# KursSCH4.net
KiCad netlist of a schematic drawn in Altium Designer
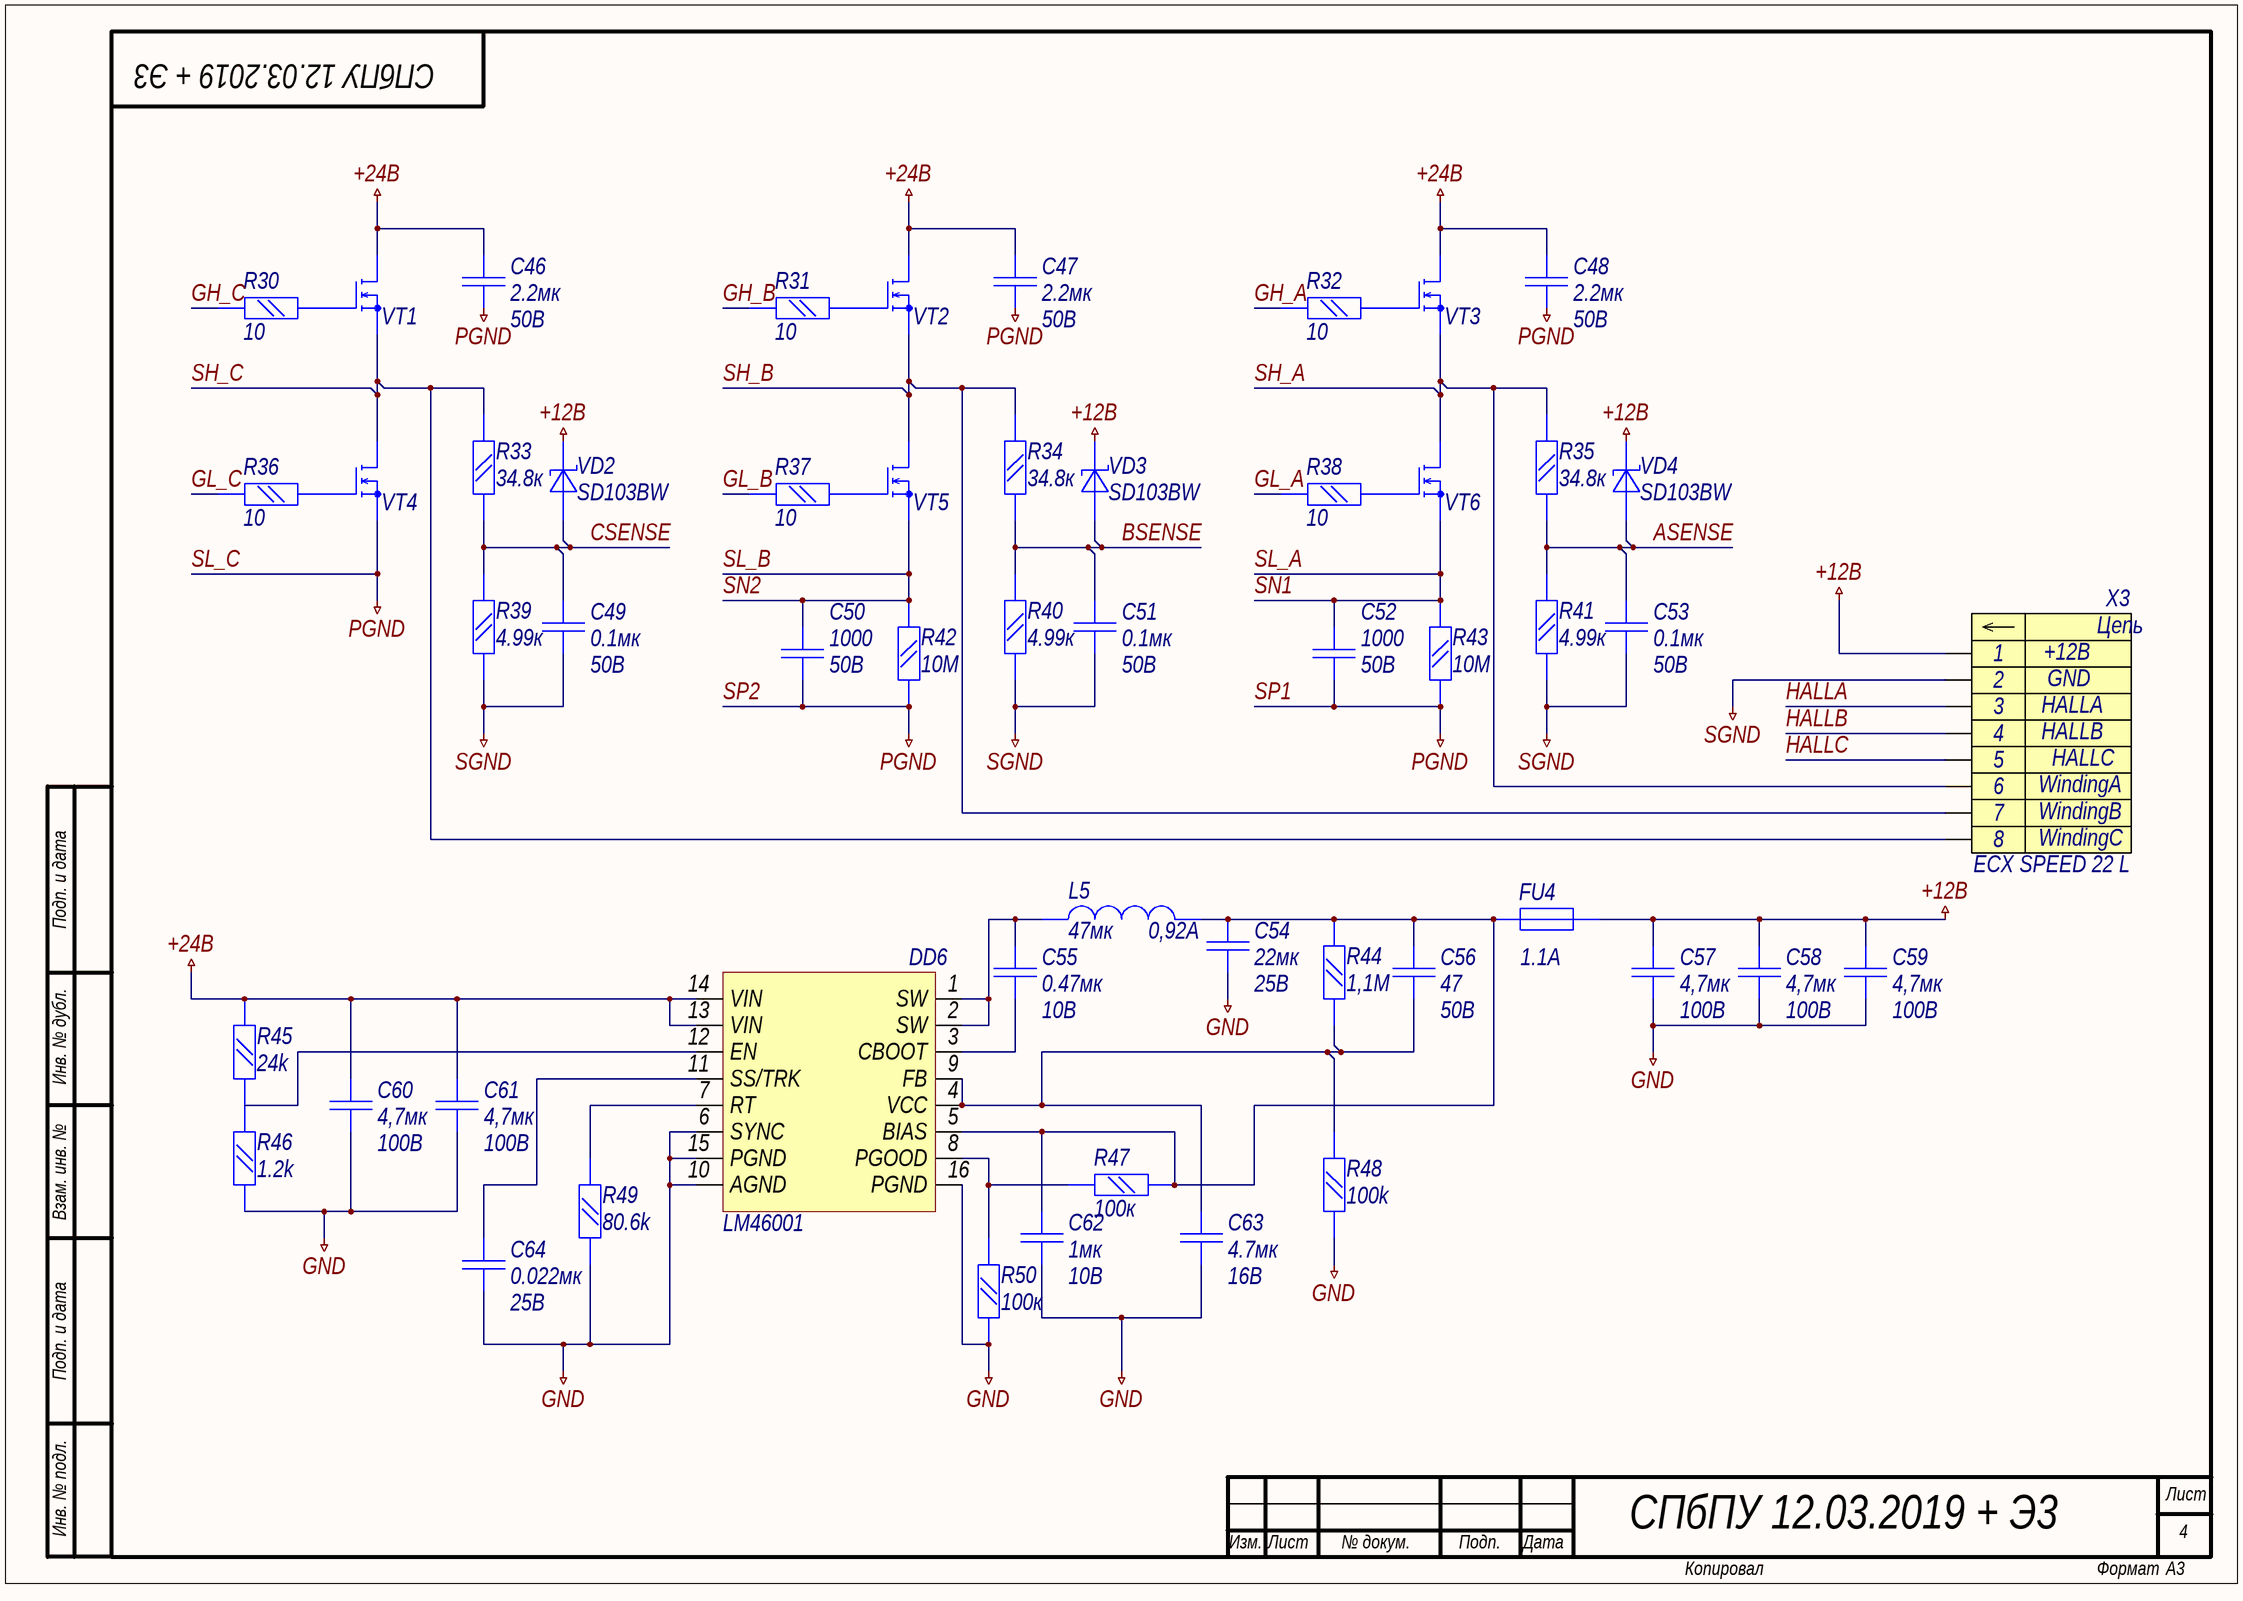
[diagram p0: KursSCH4.schdoc]

(export (version "E")
  (design (tool "Eeschema 10.0.6"))
  (components
    (comp (ref "C46")
      (value "2.2мк")
      (footprint "C0603")
      (fields
        (field (name "VOLTAGE") "50В")
        (field (name "PART NUMBER") "GRM188R61C225KE15D")
        (field (name "TOLERANCE") "±10%")
        (field (name "MANUFACTURER") "Murata")
      )
      (libsource (lib "Lib_IMP_GOST") (part "Capacitor"))
    )
    (comp (ref "C47")
      (value "2.2мк")
      (footprint "C0603")
      (fields
        (field (name "VOLTAGE") "50В")
        (field (name "PART NUMBER") "GRM188R61C225KE15D")
        (field (name "TOLERANCE") "±10%")
        (field (name "MANUFACTURER") "Murata")
      )
      (libsource (lib "Lib_IMP_GOST") (part "Capacitor"))
    )
    (comp (ref "C48")
      (value "2.2мк")
      (footprint "C0603")
      (fields
        (field (name "VOLTAGE") "50В")
        (field (name "PART NUMBER") "GRM188R61C225KE15D")
        (field (name "TOLERANCE") "±10%")
        (field (name "MANUFACTURER") "Murata")
      )
      (libsource (lib "Lib_IMP_GOST") (part "Capacitor"))
    )
    (comp (ref "C49")
      (value "0.1мк")
      (footprint "C0805")
      (fields
        (field (name "VOLTAGE") "50В")
        (field (name "PART NUMBER") "GRM21BR71H104KA01L")
        (field (name "TOLERANCE") "±10%")
        (field (name "MANUFACTURER") "Murata")
      )
      (libsource (lib "Lib_IMP_GOST") (part "Capacitor"))
    )
    (comp (ref "C50")
      (value "1000")
      (footprint "C0402")
      (fields
        (field (name "VOLTAGE") "50В")
        (field (name "PART NUMBER") "GRM155R71H102KA01D")
        (field (name "TOLERANCE") "±10%")
        (field (name "MANUFACTURER") "Murata")
      )
      (libsource (lib "Lib_IMP_GOST") (part "Capacitor"))
    )
    (comp (ref "C51")
      (value "0.1мк")
      (footprint "C0805")
      (fields
        (field (name "VOLTAGE") "50В")
        (field (name "PART NUMBER") "GRM21BR71H104KA01L")
        (field (name "TOLERANCE") "±10%")
        (field (name "MANUFACTURER") "Murata")
      )
      (libsource (lib "Lib_IMP_GOST") (part "Capacitor"))
    )
    (comp (ref "C52")
      (value "1000")
      (footprint "C0402")
      (fields
        (field (name "VOLTAGE") "50В")
        (field (name "PART NUMBER") "GRM155R71H102KA01D")
        (field (name "TOLERANCE") "±10%")
        (field (name "MANUFACTURER") "Murata")
      )
      (libsource (lib "Lib_IMP_GOST") (part "Capacitor"))
    )
    (comp (ref "C53")
      (value "0.1мк")
      (footprint "C0805")
      (fields
        (field (name "VOLTAGE") "50В")
        (field (name "PART NUMBER") "GRM21BR71H104KA01L")
        (field (name "TOLERANCE") "±10%")
        (field (name "MANUFACTURER") "Murata")
      )
      (libsource (lib "Lib_IMP_GOST") (part "Capacitor"))
    )
    (comp (ref "C54")
      (value "22мк")
      (footprint "C0805")
      (fields
        (field (name "VOLTAGE") "25В")
        (field (name "PART NUMBER") "GRM21BR61E226ME44L")
        (field (name "TOLERANCE") "±20%")
        (field (name "MANUFACTURER") "Murata")
      )
      (libsource (lib "Lib_IMP_GOST") (part "Capacitor"))
    )
    (comp (ref "C55")
      (value "0.47мк")
      (footprint "C0603")
      (fields
        (field (name "VOLTAGE") "10В")
        (field (name "PART NUMBER") "GRM188R71A474KA61D")
        (field (name "TOLERANCE") "±10%")
        (field (name "MANUFACTURER") "Murata")
      )
      (libsource (lib "Lib_IMP_GOST") (part "Capacitor"))
    )
    (comp (ref "C56")
      (value "47")
      (footprint "C0402")
      (fields
        (field (name "VOLTAGE") "50В")
        (field (name "PART NUMBER") "GRM1535C1H470JDD5D")
        (field (name "TOLERANCE") "±5%")
        (field (name "MANUFACTURER") "Murata")
      )
      (libsource (lib "Lib_IMP_GOST") (part "Capacitor"))
    )
    (comp (ref "C57")
      (value "4,7мк")
      (footprint "C1206")
      (fields
        (field (name "VOLTAGE") "100В")
        (field (name "PART NUMBER") "GRM31CC72A475ME11")
        (field (name "TOLERANCE") "±10%")
        (field (name "MANUFACTURER") "Murata")
      )
      (libsource (lib "Lib_IMP_GOST") (part "Capacitor"))
    )
    (comp (ref "C58")
      (value "4,7мк")
      (footprint "C1206")
      (fields
        (field (name "VOLTAGE") "100В")
        (field (name "PART NUMBER") "GRM31CC72A475ME11")
        (field (name "TOLERANCE") "±10%")
        (field (name "MANUFACTURER") "Murata")
      )
      (libsource (lib "Lib_IMP_GOST") (part "Capacitor"))
    )
    (comp (ref "C59")
      (value "4,7мк")
      (footprint "C1206")
      (fields
        (field (name "VOLTAGE") "100В")
        (field (name "PART NUMBER") "GRM31CC72A475ME11")
        (field (name "TOLERANCE") "±10%")
        (field (name "MANUFACTURER") "Murata")
      )
      (libsource (lib "Lib_IMP_GOST") (part "Capacitor"))
    )
    (comp (ref "C60")
      (value "4,7мк")
      (footprint "C1206")
      (fields
        (field (name "VOLTAGE") "100В")
        (field (name "PART NUMBER") "GRM31CC72A475ME11")
        (field (name "TOLERANCE") "±10%")
        (field (name "MANUFACTURER") "Murata")
      )
      (libsource (lib "Lib_IMP_GOST") (part "Capacitor"))
    )
    (comp (ref "C61")
      (value "4,7мк")
      (footprint "C1206")
      (fields
        (field (name "VOLTAGE") "100В")
        (field (name "PART NUMBER") "GRM31CC72A475ME11")
        (field (name "TOLERANCE") "±10%")
        (field (name "MANUFACTURER") "Murata")
      )
      (libsource (lib "Lib_IMP_GOST") (part "Capacitor"))
    )
    (comp (ref "C62")
      (value "1мк")
      (footprint "C0603")
      (fields
        (field (name "VOLTAGE") "10В")
        (field (name "PART NUMBER") "GRM188R61A105KA01D")
        (field (name "TOLERANCE") "±10%")
        (field (name "MANUFACTURER") "Murata")
      )
      (libsource (lib "Lib_IMP_GOST") (part "Capacitor"))
    )
    (comp (ref "C63")
      (value "4.7мк")
      (footprint "C0603")
      (fields
        (field (name "VOLTAGE") "16В")
        (field (name "PART NUMBER") "GRM188R61A475KE15D")
        (field (name "TOLERANCE") "±10%")
        (field (name "MANUFACTURER") "Murata")
      )
      (libsource (lib "Lib_IMP_GOST") (part "Capacitor"))
    )
    (comp (ref "C64")
      (value "0.022мк")
      (footprint "C0603")
      (fields
        (field (name "VOLTAGE") "25В")
        (field (name "PART NUMBER") "GRM188R71E223JA01D")
        (field (name "TOLERANCE") "±5%")
        (field (name "MANUFACTURER") "Murata")
      )
      (libsource (lib "Lib_IMP_GOST") (part "Capacitor"))
    )
    (comp (ref "DD6") (value "LM46001") (footprint "LM46001") (libsource (lib "Schlib1") (part "LM46001")))
    (comp (ref "FU4")
      (value "Fuse")
      (footprint "F1812")
      (fields (field (name "RATED CURRENT") "1.1A") (field (name "PUBLISHER") "Andrew Danich"))
      (libsource (lib "Lib_IMP_GOST") (part "Fuse"))
    )
    (comp (ref "L5")
      (value "7447779115")
      (footprint "747779115")
      (fields (field (name "I") "0,92А") (field (name "L") "47мк"))
      (libsource (lib "Schlib1") (part "7447779115"))
    )
    (comp (ref "R30")
      (value "10")
      (footprint "R0805")
      (fields
        (field (name "PART NUMBER") "RC0805JR-0710RL")
        (field (name "TOLERANCE") "±5%")
        (field (name "MANUFACTURER") "Yageo")
      )
      (libsource (lib "Lib_IMP_GOST") (part "Resistor_0,125W"))
    )
    (comp (ref "R31")
      (value "10")
      (footprint "R0805")
      (fields
        (field (name "PART NUMBER") "RC0805JR-0710RL")
        (field (name "TOLERANCE") "±5%")
        (field (name "MANUFACTURER") "Yageo")
      )
      (libsource (lib "Lib_IMP_GOST") (part "Resistor_0,125W"))
    )
    (comp (ref "R32")
      (value "10")
      (footprint "R0805")
      (fields
        (field (name "PART NUMBER") "RC0805JR-0710RL")
        (field (name "TOLERANCE") "±5%")
        (field (name "MANUFACTURER") "Yageo")
      )
      (libsource (lib "Lib_IMP_GOST") (part "Resistor_0,125W"))
    )
    (comp (ref "R33")
      (value "34.8к")
      (footprint "R0805")
      (fields
        (field (name "PART NUMBER") "RC0805FR-0734K8L")
        (field (name "TOLERANCE") "±1%")
        (field (name "MANUFACTURER") "Yageo")
      )
      (libsource (lib "Lib_IMP_GOST") (part "Resistor_0,125W"))
    )
    (comp (ref "R34")
      (value "34.8к")
      (footprint "R0805")
      (fields
        (field (name "PART NUMBER") "RC0805FR-0734K8L")
        (field (name "TOLERANCE") "±1%")
        (field (name "MANUFACTURER") "Yageo")
      )
      (libsource (lib "Lib_IMP_GOST") (part "Resistor_0,125W"))
    )
    (comp (ref "R35")
      (value "34.8к")
      (footprint "R0805")
      (fields
        (field (name "PART NUMBER") "RC0805FR-0734K8L")
        (field (name "TOLERANCE") "±1%")
        (field (name "MANUFACTURER") "Yageo")
      )
      (libsource (lib "Lib_IMP_GOST") (part "Resistor_0,125W"))
    )
    (comp (ref "R36")
      (value "10")
      (footprint "R0805")
      (fields
        (field (name "PART NUMBER") "RC0805JR-0710RL")
        (field (name "TOLERANCE") "±5%")
        (field (name "MANUFACTURER") "Yageo")
      )
      (libsource (lib "Lib_IMP_GOST") (part "Resistor_0,125W"))
    )
    (comp (ref "R37")
      (value "10")
      (footprint "R0805")
      (fields
        (field (name "PART NUMBER") "RC0805JR-0710RL")
        (field (name "TOLERANCE") "±5%")
        (field (name "MANUFACTURER") "Yageo")
      )
      (libsource (lib "Lib_IMP_GOST") (part "Resistor_0,125W"))
    )
    (comp (ref "R38")
      (value "10")
      (footprint "R0805")
      (fields
        (field (name "PART NUMBER") "RC0805JR-0710RL")
        (field (name "TOLERANCE") "±5%")
        (field (name "MANUFACTURER") "Yageo")
      )
      (libsource (lib "Lib_IMP_GOST") (part "Resistor_0,125W"))
    )
    (comp (ref "R39")
      (value "4.99к")
      (footprint "R0603")
      (fields
        (field (name "PART NUMBER") "RC0603FR-074K99L")
        (field (name "TOLERANCE") "±1%")
        (field (name "MANUFACTURER") "Yageo")
      )
      (libsource (lib "Lib_IMP_GOST") (part "Resistor_0,125W"))
    )
    (comp (ref "R40")
      (value "4.99к")
      (footprint "R0603")
      (fields
        (field (name "PART NUMBER") "RC0603FR-074K99L")
        (field (name "TOLERANCE") "±1%")
        (field (name "MANUFACTURER") "Yageo")
      )
      (libsource (lib "Lib_IMP_GOST") (part "Resistor_0,125W"))
    )
    (comp (ref "R41")
      (value "4.99к")
      (footprint "R0603")
      (fields
        (field (name "PART NUMBER") "RC0603FR-074K99L")
        (field (name "TOLERANCE") "±1%")
        (field (name "MANUFACTURER") "Yageo")
      )
      (libsource (lib "Lib_IMP_GOST") (part "Resistor_0,125W"))
    )
    (comp (ref "R42")
      (value "10М")
      (footprint "R0603")
      (fields
        (field (name "PART NUMBER") "RC0603FR-0710ML")
        (field (name "TOLERANCE") "±1%")
        (field (name "MANUFACTURER") "Yageo")
      )
      (libsource (lib "Lib_IMP_GOST") (part "Resistor_0,125W"))
    )
    (comp (ref "R43")
      (value "10М")
      (footprint "R0603")
      (fields
        (field (name "PART NUMBER") "RC0603FR-0710ML")
        (field (name "TOLERANCE") "±1%")
        (field (name "MANUFACTURER") "Yageo")
      )
      (libsource (lib "Lib_IMP_GOST") (part "Resistor_0,125W"))
    )
    (comp (ref "R44")
      (value "1,1М")
      (footprint "R0805")
      (fields
        (field (name "PART NUMBER") "RC0805JR-071M1L")
        (field (name "TOLERANCE") "±5%")
        (field (name "MANUFACTURER") "Yageo")
      )
      (libsource (lib "Lib_IMP_GOST") (part "Resistor_0,125W"))
    )
    (comp (ref "R45")
      (value "24k")
      (footprint "R0603")
      (fields
        (field (name "PART NUMBER") "RC0603JR-0724KL")
        (field (name "TOLERANCE") "±5%")
        (field (name "MANUFACTURER") "Yageo")
      )
      (libsource (lib "Lib_IMP_GOST") (part "Resistor_0,125W"))
    )
    (comp (ref "R46")
      (value "1.2k")
      (footprint "R0603")
      (fields
        (field (name "PART NUMBER") "RC0603JR-071K2L")
        (field (name "TOLERANCE") "±5%")
        (field (name "MANUFACTURER") "Yageo")
      )
      (libsource (lib "Lib_IMP_GOST") (part "Resistor_0,125W"))
    )
    (comp (ref "R47")
      (value "100к")
      (footprint "R0805")
      (fields
        (field (name "PART NUMBER") "RC0805JR-07100KL")
        (field (name "TOLERANCE") "±5%")
        (field (name "MANUFACTURER") "Yageo")
      )
      (libsource (lib "Lib_IMP_GOST") (part "Resistor_0,125W"))
    )
    (comp (ref "R48")
      (value "100k")
      (footprint "R0805")
      (fields
        (field (name "PART NUMBER") "RC0805JR-07100KL")
        (field (name "TOLERANCE") "±5%")
        (field (name "MANUFACTURER") "Yageo")
      )
      (libsource (lib "Lib_IMP_GOST") (part "Resistor_0,125W"))
    )
    (comp (ref "R49")
      (value "80.6k")
      (footprint "R0603")
      (fields
        (field (name "PART NUMBER") "RC0603FR-0780K6L")
        (field (name "TOLERANCE") "±1%")
        (field (name "MANUFACTURER") "Yageo")
      )
      (libsource (lib "Lib_IMP_GOST") (part "Resistor_0,125W"))
    )
    (comp (ref "R50")
      (value "100к")
      (footprint "R0805")
      (fields
        (field (name "PART NUMBER") "RC0805JR-07100KL")
        (field (name "TOLERANCE") "±5%")
        (field (name "MANUFACTURER") "Yageo")
      )
      (libsource (lib "Lib_IMP_GOST") (part "Resistor_0,125W"))
    )
    (comp (ref "VD2")
      (value "Schottky")
      (footprint "SOD-123")
      (fields (field (name "PART NUMBER") "SD103BW"))
      (libsource (lib "Lib_IMP_GOST") (part "Schottky"))
    )
    (comp (ref "VD3")
      (value "Schottky")
      (footprint "SOD-123")
      (fields (field (name "PART NUMBER") "SD103BW"))
      (libsource (lib "Lib_IMP_GOST") (part "Schottky"))
    )
    (comp (ref "VD4")
      (value "Schottky")
      (footprint "SOD-123")
      (fields (field (name "PART NUMBER") "SD103BW"))
      (libsource (lib "Lib_IMP_GOST") (part "Schottky"))
    )
    (comp (ref "VT1")
      (value "MOSFET-N")
      (footprint "SOT-23")
      (fields
        (field (name "PART NUMBER") "2n7002")
        (field (name "MANUFACTURER") "Diodes Incorporated")
        (field (name "PUBLISHER") "Andrew Danich")
      )
      (libsource (lib "Lib_IMP_GOST") (part "MOSFET-N"))
    )
    (comp (ref "VT2")
      (value "MOSFET-N")
      (footprint "SOT-23")
      (fields
        (field (name "PART NUMBER") "2n7002")
        (field (name "MANUFACTURER") "Diodes Incorporated")
        (field (name "PUBLISHER") "Andrew Danich")
      )
      (libsource (lib "Lib_IMP_GOST") (part "MOSFET-N"))
    )
    (comp (ref "VT3")
      (value "MOSFET-N")
      (footprint "SOT-23")
      (fields
        (field (name "PART NUMBER") "2n7002")
        (field (name "MANUFACTURER") "Diodes Incorporated")
        (field (name "PUBLISHER") "Andrew Danich")
      )
      (libsource (lib "Lib_IMP_GOST") (part "MOSFET-N"))
    )
    (comp (ref "VT4")
      (value "MOSFET-N")
      (footprint "SOT-23")
      (fields
        (field (name "PART NUMBER") "2n7002")
        (field (name "MANUFACTURER") "Diodes Incorporated")
        (field (name "PUBLISHER") "Andrew Danich")
      )
      (libsource (lib "Lib_IMP_GOST") (part "MOSFET-N"))
    )
    (comp (ref "VT5")
      (value "MOSFET-N")
      (footprint "SOT-23")
      (fields
        (field (name "PART NUMBER") "2n7002")
        (field (name "MANUFACTURER") "Diodes Incorporated")
        (field (name "PUBLISHER") "Andrew Danich")
      )
      (libsource (lib "Lib_IMP_GOST") (part "MOSFET-N"))
    )
    (comp (ref "VT6")
      (value "MOSFET-N")
      (footprint "SOT-23")
      (fields
        (field (name "PART NUMBER") "2n7002")
        (field (name "MANUFACTURER") "Diodes Incorporated")
        (field (name "PUBLISHER") "Andrew Danich")
      )
      (libsource (lib "Lib_IMP_GOST") (part "MOSFET-N"))
    )
    (comp (ref "X3")
      (value "ECX SPEED 22 L")
      (footprint "USB")
      (fields
        (field (name "U") "+12В")
        (field (name "HALL1") "HALLA")
        (field (name "HALL2") "HALLB")
        (field (name "GND") "GND")
        (field (name "HALL3") "HALLC")
        (field (name "WINDING1") "WindingA")
        (field (name "WINDING2") "WindingB")
        (field (name "WINDING3") "WindingC")
        (field (name "CREATE") "DeathSpeaker")
      )
      (libsource (lib "Schlib1") (part "ECX SPEED 22 L"))
    )
  )
  (nets
    (net (code "1") (name "+12В") (class "Default")
      (node (ref "C57") (pin "2") (pinfunction "2_2") (pintype "passive"))
      (node (ref "C58") (pin "2") (pinfunction "2_2") (pintype "passive"))
      (node (ref "C59") (pin "2") (pinfunction "2_2") (pintype "passive"))
      (node (ref "FU4") (pin "2") (pinfunction "2_2") (pintype "passive"))
      (node (ref "VD2") (pin "2") (pinfunction "К_2") (pintype "passive"))
      (node (ref "VD3") (pin "2") (pinfunction "К_2") (pintype "passive"))
      (node (ref "VD4") (pin "2") (pinfunction "К_2") (pintype "passive"))
      (node (ref "X3") (pin "1") (pinfunction "1_1") (pintype "passive"))
    )
    (net (code "2") (name "+24В") (class "Default")
      (node (ref "C46") (pin "2") (pinfunction "2_2") (pintype "passive"))
      (node (ref "C47") (pin "2") (pinfunction "2_2") (pintype "passive"))
      (node (ref "C48") (pin "2") (pinfunction "2_2") (pintype "passive"))
      (node (ref "C60") (pin "2") (pinfunction "2_2") (pintype "passive"))
      (node (ref "C61") (pin "2") (pinfunction "2_2") (pintype "passive"))
      (node (ref "DD6") (pin "13") (pinfunction "VIN_13") (pintype "passive"))
      (node (ref "DD6") (pin "14") (pinfunction "VIN_14") (pintype "passive"))
      (node (ref "R45") (pin "2") (pinfunction "2_2") (pintype "passive"))
      (node (ref "VT1") (pin "2") (pinfunction "D_2") (pintype "passive"))
      (node (ref "VT2") (pin "2") (pinfunction "D_2") (pintype "passive"))
      (node (ref "VT3") (pin "2") (pinfunction "D_2") (pintype "passive"))
    )
    (net (code "3") (name "/ASENSE") (class "Default")
      (node (ref "C53") (pin "2") (pinfunction "2_2") (pintype "passive"))
      (node (ref "R35") (pin "1") (pinfunction "1_1") (pintype "passive"))
      (node (ref "R41") (pin "2") (pinfunction "2_2") (pintype "passive"))
      (node (ref "VD4") (pin "1") (pinfunction "А_1") (pintype "passive"))
    )
    (net (code "4") (name "/BSENSE") (class "Default")
      (node (ref "C51") (pin "2") (pinfunction "2_2") (pintype "passive"))
      (node (ref "R34") (pin "1") (pinfunction "1_1") (pintype "passive"))
      (node (ref "R40") (pin "2") (pinfunction "2_2") (pintype "passive"))
      (node (ref "VD3") (pin "1") (pinfunction "А_1") (pintype "passive"))
    )
    (net (code "5") (name "/CSENSE") (class "Default")
      (node (ref "C49") (pin "2") (pinfunction "2_2") (pintype "passive"))
      (node (ref "R33") (pin "1") (pinfunction "1_1") (pintype "passive"))
      (node (ref "R39") (pin "2") (pinfunction "2_2") (pintype "passive"))
      (node (ref "VD2") (pin "1") (pinfunction "А_1") (pintype "passive"))
    )
    (net (code "6") (name "/GH_A") (class "Default")
      (node (ref "R32") (pin "1") (pinfunction "1_1") (pintype "passive"))
    )
    (net (code "7") (name "/GH_B") (class "Default")
      (node (ref "R31") (pin "1") (pinfunction "1_1") (pintype "passive"))
    )
    (net (code "8") (name "/GH_C") (class "Default")
      (node (ref "R30") (pin "1") (pinfunction "1_1") (pintype "passive"))
    )
    (net (code "9") (name "/GL_A") (class "Default")
      (node (ref "R38") (pin "1") (pinfunction "1_1") (pintype "passive"))
    )
    (net (code "10") (name "/GL_B") (class "Default")
      (node (ref "R37") (pin "1") (pinfunction "1_1") (pintype "passive"))
    )
    (net (code "11") (name "/GL_C") (class "Default")
      (node (ref "R36") (pin "1") (pinfunction "1_1") (pintype "passive"))
    )
    (net (code "12") (name "/HALLA") (class "Default")
      (node (ref "X3") (pin "3") (pinfunction "3_3") (pintype "passive"))
    )
    (net (code "13") (name "/HALLB") (class "Default")
      (node (ref "X3") (pin "4") (pinfunction "4_4") (pintype "passive"))
    )
    (net (code "14") (name "/HALLC") (class "Default")
      (node (ref "X3") (pin "5") (pinfunction "5_5") (pintype "passive"))
    )
    (net (code "15") (name "/SH_A") (class "Default")
      (node (ref "R35") (pin "2") (pinfunction "2_2") (pintype "passive"))
      (node (ref "VT3") (pin "3") (pinfunction "S_3") (pintype "passive"))
      (node (ref "VT6") (pin "2") (pinfunction "D_2") (pintype "passive"))
      (node (ref "X3") (pin "6") (pinfunction "6_6") (pintype "passive"))
    )
    (net (code "16") (name "/SH_B") (class "Default")
      (node (ref "R34") (pin "2") (pinfunction "2_2") (pintype "passive"))
      (node (ref "VT2") (pin "3") (pinfunction "S_3") (pintype "passive"))
      (node (ref "VT5") (pin "2") (pinfunction "D_2") (pintype "passive"))
      (node (ref "X3") (pin "7") (pinfunction "7_7") (pintype "passive"))
    )
    (net (code "17") (name "/SH_C") (class "Default")
      (node (ref "R33") (pin "2") (pinfunction "2_2") (pintype "passive"))
      (node (ref "VT1") (pin "3") (pinfunction "S_3") (pintype "passive"))
      (node (ref "VT4") (pin "2") (pinfunction "D_2") (pintype "passive"))
      (node (ref "X3") (pin "8") (pinfunction "8_8") (pintype "passive"))
    )
    (net (code "18") (name "/SL_A") (class "Default")
      (node (ref "C52") (pin "2") (pinfunction "2_2") (pintype "passive"))
      (node (ref "R43") (pin "2") (pinfunction "2_2") (pintype "passive"))
      (node (ref "VT6") (pin "3") (pinfunction "S_3") (pintype "passive"))
    )
    (net (code "19") (name "/SL_B") (class "Default")
      (node (ref "C50") (pin "2") (pinfunction "2_2") (pintype "passive"))
      (node (ref "R42") (pin "2") (pinfunction "2_2") (pintype "passive"))
      (node (ref "VT5") (pin "3") (pinfunction "S_3") (pintype "passive"))
    )
    (net (code "20") (name "GND") (class "Default")
      (node (ref "C54") (pin "1") (pinfunction "1_1") (pintype "passive"))
      (node (ref "C57") (pin "1") (pinfunction "1_1") (pintype "passive"))
      (node (ref "C58") (pin "1") (pinfunction "1_1") (pintype "passive"))
      (node (ref "C59") (pin "1") (pinfunction "1_1") (pintype "passive"))
      (node (ref "C60") (pin "1") (pinfunction "1_1") (pintype "passive"))
      (node (ref "C61") (pin "1") (pinfunction "1_1") (pintype "passive"))
      (node (ref "C62") (pin "1") (pinfunction "1_1") (pintype "passive"))
      (node (ref "C63") (pin "1") (pinfunction "1_1") (pintype "passive"))
      (node (ref "C64") (pin "2") (pinfunction "2_2") (pintype "passive"))
      (node (ref "DD6") (pin "10") (pinfunction "AGND_10") (pintype "passive"))
      (node (ref "DD6") (pin "15") (pinfunction "PGND_15") (pintype "passive"))
      (node (ref "DD6") (pin "16") (pinfunction "PGND_16") (pintype "passive"))
      (node (ref "DD6") (pin "6") (pinfunction "SYNC_6") (pintype "passive"))
      (node (ref "R46") (pin "1") (pinfunction "1_1") (pintype "passive"))
      (node (ref "R48") (pin "1") (pinfunction "1_1") (pintype "passive"))
      (node (ref "R49") (pin "1") (pinfunction "1_1") (pintype "passive"))
      (node (ref "R50") (pin "1") (pinfunction "1_1") (pintype "passive"))
    )
    (net (code "21") (name "Net-(C55-Pad2)") (class "Default")
      (node (ref "C55") (pin "2") (pinfunction "2_2") (pintype "passive"))
      (node (ref "DD6") (pin "1") (pinfunction "SW_1") (pintype "passive"))
      (node (ref "DD6") (pin "2") (pinfunction "SW_2") (pintype "passive"))
      (node (ref "L5") (pin "1") (pinfunction "1_1") (pintype "passive"))
    )
    (net (code "22") (name "Net-(DD6-BIAS)") (class "Default")
      (node (ref "C54") (pin "2") (pinfunction "2_2") (pintype "passive"))
      (node (ref "C56") (pin "2") (pinfunction "2_2") (pintype "passive"))
      (node (ref "C62") (pin "2") (pinfunction "2_2") (pintype "passive"))
      (node (ref "DD6") (pin "5") (pinfunction "BIAS_5") (pintype "passive"))
      (node (ref "FU4") (pin "1") (pinfunction "1_1") (pintype "passive"))
      (node (ref "L5") (pin "2") (pinfunction "2_2") (pintype "passive"))
      (node (ref "R44") (pin "2") (pinfunction "2_2") (pintype "passive"))
      (node (ref "R47") (pin "2") (pinfunction "2_2") (pintype "passive"))
    )
    (net (code "23") (name "Net-(DD6-CBOOT)") (class "Default")
      (node (ref "C55") (pin "1") (pinfunction "1_1") (pintype "passive"))
      (node (ref "DD6") (pin "3") (pinfunction "CBOOT_3") (pintype "passive"))
    )
    (net (code "24") (name "Net-(DD6-EN)") (class "Default")
      (node (ref "DD6") (pin "12") (pinfunction "EN_12") (pintype "passive"))
      (node (ref "R45") (pin "1") (pinfunction "1_1") (pintype "passive"))
      (node (ref "R46") (pin "2") (pinfunction "2_2") (pintype "passive"))
    )
    (net (code "25") (name "Net-(DD6-FB)") (class "Default")
      (node (ref "C56") (pin "1") (pinfunction "1_1") (pintype "passive"))
      (node (ref "C63") (pin "2") (pinfunction "2_2") (pintype "passive"))
      (node (ref "DD6") (pin "4") (pinfunction "VCC_4") (pintype "passive"))
      (node (ref "DD6") (pin "9") (pinfunction "FB_9") (pintype "passive"))
      (node (ref "R44") (pin "1") (pinfunction "1_1") (pintype "passive"))
      (node (ref "R48") (pin "2") (pinfunction "2_2") (pintype "passive"))
    )
    (net (code "26") (name "Net-(DD6-PGOOD)") (class "Default")
      (node (ref "DD6") (pin "8") (pinfunction "PGOOD_8") (pintype "passive"))
      (node (ref "R47") (pin "1") (pinfunction "1_1") (pintype "passive"))
      (node (ref "R50") (pin "2") (pinfunction "2_2") (pintype "passive"))
    )
    (net (code "27") (name "Net-(DD6-RT)") (class "Default")
      (node (ref "DD6") (pin "7") (pinfunction "RT_7") (pintype "passive"))
      (node (ref "R49") (pin "2") (pinfunction "2_2") (pintype "passive"))
    )
    (net (code "28") (name "Net-(DD6-SS{slash}TRK)") (class "Default")
      (node (ref "C64") (pin "1") (pinfunction "1_1") (pintype "passive"))
      (node (ref "DD6") (pin "11") (pinfunction "SS/TRK_11") (pintype "passive"))
    )
    (net (code "29") (name "Net-(VT1-G)") (class "Default")
      (node (ref "R30") (pin "2") (pinfunction "2_2") (pintype "passive"))
      (node (ref "VT1") (pin "1") (pinfunction "G_1") (pintype "passive"))
    )
    (net (code "30") (name "Net-(VT2-G)") (class "Default")
      (node (ref "R31") (pin "2") (pinfunction "2_2") (pintype "passive"))
      (node (ref "VT2") (pin "1") (pinfunction "G_1") (pintype "passive"))
    )
    (net (code "31") (name "Net-(VT3-G)") (class "Default")
      (node (ref "R32") (pin "2") (pinfunction "2_2") (pintype "passive"))
      (node (ref "VT3") (pin "1") (pinfunction "G_1") (pintype "passive"))
    )
    (net (code "32") (name "Net-(VT4-G)") (class "Default")
      (node (ref "R36") (pin "2") (pinfunction "2_2") (pintype "passive"))
      (node (ref "VT4") (pin "1") (pinfunction "G_1") (pintype "passive"))
    )
    (net (code "33") (name "Net-(VT5-G)") (class "Default")
      (node (ref "R37") (pin "2") (pinfunction "2_2") (pintype "passive"))
      (node (ref "VT5") (pin "1") (pinfunction "G_1") (pintype "passive"))
    )
    (net (code "34") (name "Net-(VT6-G)") (class "Default")
      (node (ref "R38") (pin "2") (pinfunction "2_2") (pintype "passive"))
      (node (ref "VT6") (pin "1") (pinfunction "G_1") (pintype "passive"))
    )
    (net (code "35") (name "PGND") (class "Default")
      (node (ref "C46") (pin "1") (pinfunction "1_1") (pintype "passive"))
      (node (ref "C47") (pin "1") (pinfunction "1_1") (pintype "passive"))
      (node (ref "C48") (pin "1") (pinfunction "1_1") (pintype "passive"))
      (node (ref "C50") (pin "1") (pinfunction "1_1") (pintype "passive"))
      (node (ref "C52") (pin "1") (pinfunction "1_1") (pintype "passive"))
      (node (ref "R42") (pin "1") (pinfunction "1_1") (pintype "passive"))
      (node (ref "R43") (pin "1") (pinfunction "1_1") (pintype "passive"))
      (node (ref "VT4") (pin "3") (pinfunction "S_3") (pintype "passive"))
    )
    (net (code "36") (name "SGND") (class "Default")
      (node (ref "C49") (pin "1") (pinfunction "1_1") (pintype "passive"))
      (node (ref "C51") (pin "1") (pinfunction "1_1") (pintype "passive"))
      (node (ref "C53") (pin "1") (pinfunction "1_1") (pintype "passive"))
      (node (ref "R39") (pin "1") (pinfunction "1_1") (pintype "passive"))
      (node (ref "R40") (pin "1") (pinfunction "1_1") (pintype "passive"))
      (node (ref "R41") (pin "1") (pinfunction "1_1") (pintype "passive"))
      (node (ref "X3") (pin "2") (pinfunction "2_2") (pintype "passive"))
    )
  )
)
